# ecocar_CVM.net
KiCad netlist of a schematic drawn in EAGLE
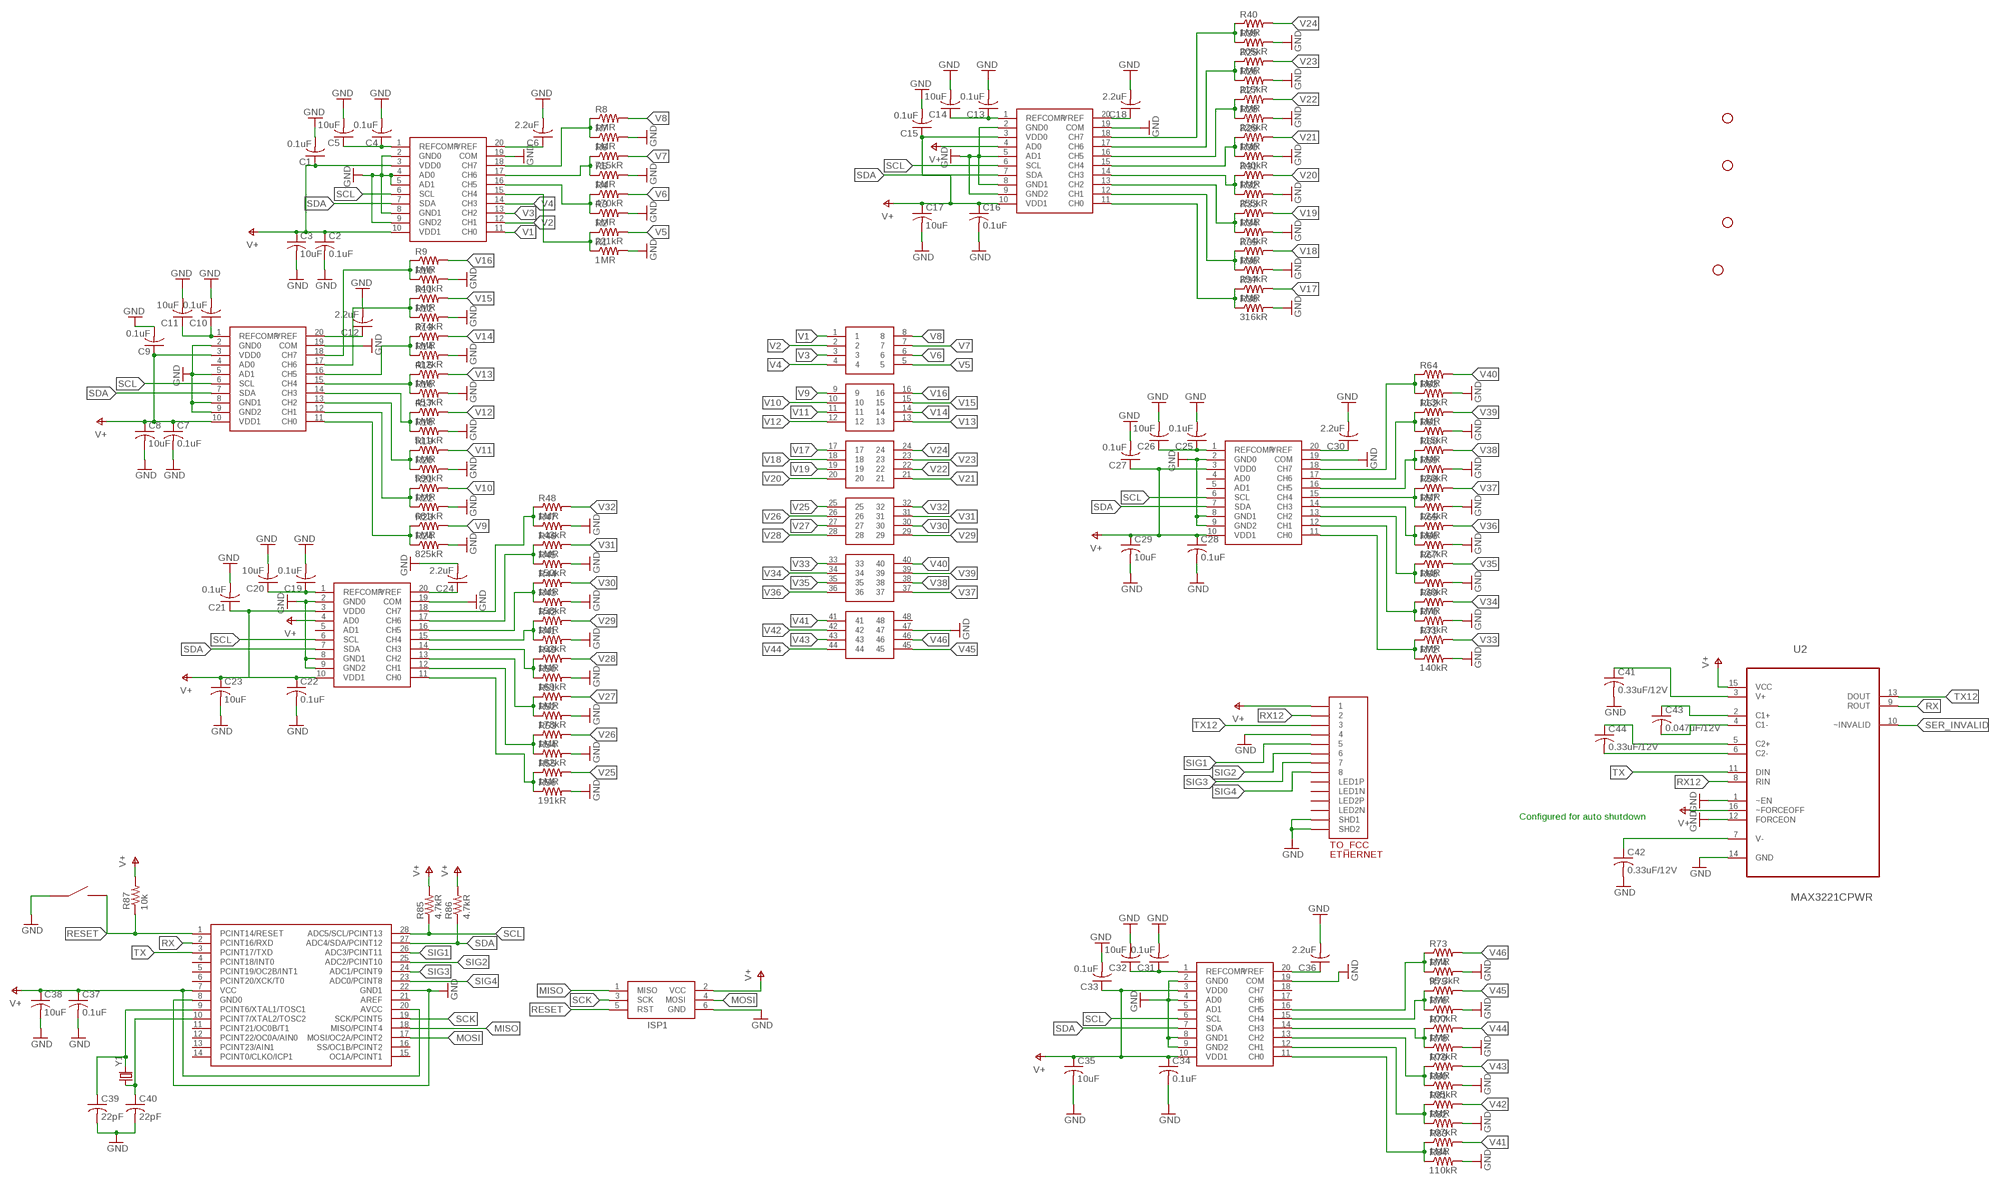
[diagram p0: schematic, sheet 1]

(export (version "E")
  (design (tool "Eeschema 10.0.6"))
  (components
    (comp (ref "0001000")
      (value "LTC2309")
      (footprint "eagle-import:TSSOP20")
      (libsource (lib "eagle-import") (part "LTC2309HF#PBF"))
    )
    (comp (ref "0001001")
      (value "LTC2309")
      (footprint "eagle-import:TSSOP20")
      (libsource (lib "eagle-import") (part "LTC2309HF#PBF"))
    )
    (comp (ref "0001010")
      (value "LTC2309")
      (footprint "eagle-import:TSSOP20")
      (libsource (lib "eagle-import") (part "LTC2309HF#PBF"))
    )
    (comp (ref "0001011")
      (value "LTC2309")
      (footprint "eagle-import:TSSOP20")
      (libsource (lib "eagle-import") (part "LTC2309HF#PBF"))
    )
    (comp (ref "0011000")
      (value "LTC2309")
      (footprint "eagle-import:TSSOP20")
      (libsource (lib "eagle-import") (part "LTC2309HF#PBF"))
    )
    (comp (ref "0011001")
      (value "LTC2309")
      (footprint "eagle-import:TSSOP20")
      (libsource (lib "eagle-import") (part "LTC2309HF#PBF"))
    )
    (comp (ref "C1")
      (value "0.1uF")
      (footprint "eagle-import:C0805")
      (libsource (lib "eagle-import") (part "rcl_C-USC0805"))
    )
    (comp (ref "C2")
      (value "0.1uF")
      (footprint "eagle-import:C0805")
      (libsource (lib "eagle-import") (part "rcl_C-USC0805"))
    )
    (comp (ref "C3")
      (value "10uF")
      (footprint "eagle-import:C0805")
      (libsource (lib "eagle-import") (part "rcl_C-USC0805"))
    )
    (comp (ref "C4")
      (value "0.1uF")
      (footprint "eagle-import:C0805")
      (libsource (lib "eagle-import") (part "rcl_C-USC0805"))
    )
    (comp (ref "C5")
      (value "10uF")
      (footprint "eagle-import:C0805")
      (libsource (lib "eagle-import") (part "rcl_C-USC0805"))
    )
    (comp (ref "C6")
      (value "2.2uF")
      (footprint "eagle-import:C0805")
      (libsource (lib "eagle-import") (part "rcl_C-USC0805"))
    )
    (comp (ref "C7")
      (value "0.1uF")
      (footprint "eagle-import:C0805")
      (libsource (lib "eagle-import") (part "rcl_C-USC0805"))
    )
    (comp (ref "C8")
      (value "10uF")
      (footprint "eagle-import:C0805")
      (libsource (lib "eagle-import") (part "rcl_C-USC0805"))
    )
    (comp (ref "C9")
      (value "0.1uF")
      (footprint "eagle-import:C0805")
      (libsource (lib "eagle-import") (part "rcl_C-USC0805"))
    )
    (comp (ref "C10")
      (value "0.1uF")
      (footprint "eagle-import:C0805")
      (libsource (lib "eagle-import") (part "rcl_C-USC0805"))
    )
    (comp (ref "C11")
      (value "10uF")
      (footprint "eagle-import:C0805")
      (libsource (lib "eagle-import") (part "rcl_C-USC0805"))
    )
    (comp (ref "C12")
      (value "2.2uF")
      (footprint "eagle-import:C0805")
      (libsource (lib "eagle-import") (part "rcl_C-USC0805"))
    )
    (comp (ref "C13")
      (value "0.1uF")
      (footprint "eagle-import:C0805")
      (libsource (lib "eagle-import") (part "rcl_C-USC0805"))
    )
    (comp (ref "C14")
      (value "10uF")
      (footprint "eagle-import:C0805")
      (libsource (lib "eagle-import") (part "rcl_C-USC0805"))
    )
    (comp (ref "C15")
      (value "0.1uF")
      (footprint "eagle-import:C0805")
      (libsource (lib "eagle-import") (part "rcl_C-USC0805"))
    )
    (comp (ref "C16")
      (value "0.1uF")
      (footprint "eagle-import:C0805")
      (libsource (lib "eagle-import") (part "rcl_C-USC0805"))
    )
    (comp (ref "C17")
      (value "10uF")
      (footprint "eagle-import:C0805")
      (libsource (lib "eagle-import") (part "rcl_C-USC0805"))
    )
    (comp (ref "C18")
      (value "2.2uF")
      (footprint "eagle-import:C0805")
      (libsource (lib "eagle-import") (part "rcl_C-USC0805"))
    )
    (comp (ref "C19")
      (value "0.1uF")
      (footprint "eagle-import:C0805")
      (libsource (lib "eagle-import") (part "rcl_C-USC0805"))
    )
    (comp (ref "C20")
      (value "10uF")
      (footprint "eagle-import:C0805")
      (libsource (lib "eagle-import") (part "rcl_C-USC0805"))
    )
    (comp (ref "C21")
      (value "0.1uF")
      (footprint "eagle-import:C0805")
      (libsource (lib "eagle-import") (part "rcl_C-USC0805"))
    )
    (comp (ref "C22")
      (value "0.1uF")
      (footprint "eagle-import:C0805")
      (libsource (lib "eagle-import") (part "rcl_C-USC0805"))
    )
    (comp (ref "C23")
      (value "10uF")
      (footprint "eagle-import:C0805")
      (libsource (lib "eagle-import") (part "rcl_C-USC0805"))
    )
    (comp (ref "C24")
      (value "2.2uF")
      (footprint "eagle-import:C0805")
      (libsource (lib "eagle-import") (part "rcl_C-USC0805"))
    )
    (comp (ref "C25")
      (value "0.1uF")
      (footprint "eagle-import:C0805")
      (libsource (lib "eagle-import") (part "rcl_C-USC0805"))
    )
    (comp (ref "C26")
      (value "10uF")
      (footprint "eagle-import:C0805")
      (libsource (lib "eagle-import") (part "rcl_C-USC0805"))
    )
    (comp (ref "C27")
      (value "0.1uF")
      (footprint "eagle-import:C0805")
      (libsource (lib "eagle-import") (part "rcl_C-USC0805"))
    )
    (comp (ref "C28")
      (value "0.1uF")
      (footprint "eagle-import:C0805")
      (libsource (lib "eagle-import") (part "rcl_C-USC0805"))
    )
    (comp (ref "C29")
      (value "10uF")
      (footprint "eagle-import:C0805")
      (libsource (lib "eagle-import") (part "rcl_C-USC0805"))
    )
    (comp (ref "C30")
      (value "2.2uF")
      (footprint "eagle-import:C0805")
      (libsource (lib "eagle-import") (part "rcl_C-USC0805"))
    )
    (comp (ref "C31")
      (value "0.1uF")
      (footprint "eagle-import:C0805")
      (libsource (lib "eagle-import") (part "rcl_C-USC0805"))
    )
    (comp (ref "C32")
      (value "10uF")
      (footprint "eagle-import:C0805")
      (libsource (lib "eagle-import") (part "rcl_C-USC0805"))
    )
    (comp (ref "C33")
      (value "0.1uF")
      (footprint "eagle-import:C0805")
      (libsource (lib "eagle-import") (part "rcl_C-USC0805"))
    )
    (comp (ref "C34")
      (value "0.1uF")
      (footprint "eagle-import:C0805")
      (libsource (lib "eagle-import") (part "rcl_C-USC0805"))
    )
    (comp (ref "C35")
      (value "10uF")
      (footprint "eagle-import:C0805")
      (libsource (lib "eagle-import") (part "rcl_C-USC0805"))
    )
    (comp (ref "C36")
      (value "2.2uF")
      (footprint "eagle-import:C0805")
      (libsource (lib "eagle-import") (part "rcl_C-USC0805"))
    )
    (comp (ref "C37")
      (value "0.1uF")
      (footprint "eagle-import:C0805")
      (libsource (lib "eagle-import") (part "rcl_C-USC0805"))
    )
    (comp (ref "C38")
      (value "10uF")
      (footprint "eagle-import:C0805")
      (libsource (lib "eagle-import") (part "rcl_C-USC0805"))
    )
    (comp (ref "C39")
      (value "22pF")
      (footprint "eagle-import:C0805")
      (libsource (lib "eagle-import") (part "rcl_C-USC0805"))
    )
    (comp (ref "C40")
      (value "22pF")
      (footprint "eagle-import:C0805")
      (libsource (lib "eagle-import") (part "rcl_C-USC0805"))
    )
    (comp (ref "C41")
      (value "0.33uF/12V")
      (footprint "eagle-import:C0805")
      (libsource (lib "eagle-import") (part "C-USC0805"))
    )
    (comp (ref "C42")
      (value "0.33uF/12V")
      (footprint "eagle-import:C0805")
      (libsource (lib "eagle-import") (part "C-USC0805"))
    )
    (comp (ref "C43")
      (value "0.047uF/12V")
      (footprint "eagle-import:C0805")
      (libsource (lib "eagle-import") (part "C-USC0805"))
    )
    (comp (ref "C44")
      (value "0.33uF/12V")
      (footprint "eagle-import:C0805")
      (libsource (lib "eagle-import") (part "C-USC0805"))
    )
    (comp (ref "ISP1")
      (value "AVRISP-BOX")
      (footprint "eagle-import:AVRISP-BOX")
      (libsource (lib "eagle-import") (part "AVRISP-BOX"))
    )
    (comp (ref "R1")
      (value "1MR")
      (footprint "eagle-import:R0805")
      (libsource (lib "eagle-import") (part "R-US_R0805"))
    )
    (comp (ref "R2")
      (value "221kR")
      (footprint "eagle-import:R0805")
      (libsource (lib "eagle-import") (part "R-US_R0805"))
    )
    (comp (ref "R3")
      (value "1MR")
      (footprint "eagle-import:R0805")
      (libsource (lib "eagle-import") (part "R-US_R0805"))
    )
    (comp (ref "R4")
      (value "470kR")
      (footprint "eagle-import:R0805")
      (libsource (lib "eagle-import") (part "R-US_R0805"))
    )
    (comp (ref "R5")
      (value "1MR")
      (footprint "eagle-import:R0805")
      (libsource (lib "eagle-import") (part "R-US_R0805"))
    )
    (comp (ref "R6")
      (value "715kR")
      (footprint "eagle-import:R0805")
      (libsource (lib "eagle-import") (part "R-US_R0805"))
    )
    (comp (ref "R7")
      (value "1MR")
      (footprint "eagle-import:R0805")
      (libsource (lib "eagle-import") (part "R-US_R0805"))
    )
    (comp (ref "R8")
      (value "1MR")
      (footprint "eagle-import:R0805")
      (libsource (lib "eagle-import") (part "R-US_R0805"))
    )
    (comp (ref "R9")
      (value "1MR")
      (footprint "eagle-import:R0805")
      (libsource (lib "eagle-import") (part "R-US_R0805"))
    )
    (comp (ref "R10")
      (value "340kR")
      (footprint "eagle-import:R0805")
      (libsource (lib "eagle-import") (part "R-US_R0805"))
    )
    (comp (ref "R11")
      (value "1MR")
      (footprint "eagle-import:R0805")
      (libsource (lib "eagle-import") (part "R-US_R0805"))
    )
    (comp (ref "R12")
      (value "374kR")
      (footprint "eagle-import:R0805")
      (libsource (lib "eagle-import") (part "R-US_R0805"))
    )
    (comp (ref "R13")
      (value "1MR")
      (footprint "eagle-import:R0805")
      (libsource (lib "eagle-import") (part "R-US_R0805"))
    )
    (comp (ref "R14")
      (value "412kR")
      (footprint "eagle-import:R0805")
      (libsource (lib "eagle-import") (part "R-US_R0805"))
    )
    (comp (ref "R15")
      (value "1MR")
      (footprint "eagle-import:R0805")
      (libsource (lib "eagle-import") (part "R-US_R0805"))
    )
    (comp (ref "R16")
      (value "453kR")
      (footprint "eagle-import:R0805")
      (libsource (lib "eagle-import") (part "R-US_R0805"))
    )
    (comp (ref "R17")
      (value "1MR")
      (footprint "eagle-import:R0805")
      (libsource (lib "eagle-import") (part "R-US_R0805"))
    )
    (comp (ref "R18")
      (value "511kR")
      (footprint "eagle-import:R0805")
      (libsource (lib "eagle-import") (part "R-US_R0805"))
    )
    (comp (ref "R19")
      (value "1MR")
      (footprint "eagle-import:R0805")
      (libsource (lib "eagle-import") (part "R-US_R0805"))
    )
    (comp (ref "R20")
      (value "590kR")
      (footprint "eagle-import:R0805")
      (libsource (lib "eagle-import") (part "R-US_R0805"))
    )
    (comp (ref "R21")
      (value "1MR")
      (footprint "eagle-import:R0805")
      (libsource (lib "eagle-import") (part "R-US_R0805"))
    )
    (comp (ref "R22")
      (value "681kR")
      (footprint "eagle-import:R0805")
      (libsource (lib "eagle-import") (part "R-US_R0805"))
    )
    (comp (ref "R23")
      (value "1MR")
      (footprint "eagle-import:R0805")
      (libsource (lib "eagle-import") (part "R-US_R0805"))
    )
    (comp (ref "R24")
      (value "825kR")
      (footprint "eagle-import:R0805")
      (libsource (lib "eagle-import") (part "R-US_R0805"))
    )
    (comp (ref "R25")
      (value "1MR")
      (footprint "eagle-import:R0805")
      (libsource (lib "eagle-import") (part "R-US_R0805"))
    )
    (comp (ref "R26")
      (value "215kR")
      (footprint "eagle-import:R0805")
      (libsource (lib "eagle-import") (part "R-US_R0805"))
    )
    (comp (ref "R27")
      (value "1MR")
      (footprint "eagle-import:R0805")
      (libsource (lib "eagle-import") (part "R-US_R0805"))
    )
    (comp (ref "R28")
      (value "226kR")
      (footprint "eagle-import:R0805")
      (libsource (lib "eagle-import") (part "R-US_R0805"))
    )
    (comp (ref "R29")
      (value "1MR")
      (footprint "eagle-import:R0805")
      (libsource (lib "eagle-import") (part "R-US_R0805"))
    )
    (comp (ref "R30")
      (value "240kR")
      (footprint "eagle-import:R0805")
      (libsource (lib "eagle-import") (part "R-US_R0805"))
    )
    (comp (ref "R31")
      (value "1MR")
      (footprint "eagle-import:R0805")
      (libsource (lib "eagle-import") (part "R-US_R0805"))
    )
    (comp (ref "R32")
      (value "255kR")
      (footprint "eagle-import:R0805")
      (libsource (lib "eagle-import") (part "R-US_R0805"))
    )
    (comp (ref "R33")
      (value "1MR")
      (footprint "eagle-import:R0805")
      (libsource (lib "eagle-import") (part "R-US_R0805"))
    )
    (comp (ref "R34")
      (value "274kR")
      (footprint "eagle-import:R0805")
      (libsource (lib "eagle-import") (part "R-US_R0805"))
    )
    (comp (ref "R35")
      (value "1MR")
      (footprint "eagle-import:R0805")
      (libsource (lib "eagle-import") (part "R-US_R0805"))
    )
    (comp (ref "R36")
      (value "294kR")
      (footprint "eagle-import:R0805")
      (libsource (lib "eagle-import") (part "R-US_R0805"))
    )
    (comp (ref "R37")
      (value "1MR")
      (footprint "eagle-import:R0805")
      (libsource (lib "eagle-import") (part "R-US_R0805"))
    )
    (comp (ref "R38")
      (value "316kR")
      (footprint "eagle-import:R0805")
      (libsource (lib "eagle-import") (part "R-US_R0805"))
    )
    (comp (ref "R39")
      (value "205kR")
      (footprint "eagle-import:R0805")
      (libsource (lib "eagle-import") (part "R-US_R0805"))
    )
    (comp (ref "R40")
      (value "1MR")
      (footprint "eagle-import:R0805")
      (libsource (lib "eagle-import") (part "R-US_R0805"))
    )
    (comp (ref "R41")
      (value "162kR")
      (footprint "eagle-import:R0805")
      (libsource (lib "eagle-import") (part "R-US_R0805"))
    )
    (comp (ref "R42")
      (value "1MR")
      (footprint "eagle-import:R0805")
      (libsource (lib "eagle-import") (part "R-US_R0805"))
    )
    (comp (ref "R43")
      (value "158kR")
      (footprint "eagle-import:R0805")
      (libsource (lib "eagle-import") (part "R-US_R0805"))
    )
    (comp (ref "R44")
      (value "1MR")
      (footprint "eagle-import:R0805")
      (libsource (lib "eagle-import") (part "R-US_R0805"))
    )
    (comp (ref "R45")
      (value "150kR")
      (footprint "eagle-import:R0805")
      (libsource (lib "eagle-import") (part "R-US_R0805"))
    )
    (comp (ref "R46")
      (value "1MR")
      (footprint "eagle-import:R0805")
      (libsource (lib "eagle-import") (part "R-US_R0805"))
    )
    (comp (ref "R47")
      (value "143kR")
      (footprint "eagle-import:R0805")
      (libsource (lib "eagle-import") (part "R-US_R0805"))
    )
    (comp (ref "R48")
      (value "1MR")
      (footprint "eagle-import:R0805")
      (libsource (lib "eagle-import") (part "R-US_R0805"))
    )
    (comp (ref "R49")
      (value "1MR")
      (footprint "eagle-import:R0805")
      (libsource (lib "eagle-import") (part "R-US_R0805"))
    )
    (comp (ref "R50")
      (value "169kR")
      (footprint "eagle-import:R0805")
      (libsource (lib "eagle-import") (part "R-US_R0805"))
    )
    (comp (ref "R51")
      (value "1MR")
      (footprint "eagle-import:R0805")
      (libsource (lib "eagle-import") (part "R-US_R0805"))
    )
    (comp (ref "R52")
      (value "178kR")
      (footprint "eagle-import:R0805")
      (libsource (lib "eagle-import") (part "R-US_R0805"))
    )
    (comp (ref "R53")
      (value "1MR")
      (footprint "eagle-import:R0805")
      (libsource (lib "eagle-import") (part "R-US_R0805"))
    )
    (comp (ref "R54")
      (value "182kR")
      (footprint "eagle-import:R0805")
      (libsource (lib "eagle-import") (part "R-US_R0805"))
    )
    (comp (ref "R55")
      (value "1MR")
      (footprint "eagle-import:R0805")
      (libsource (lib "eagle-import") (part "R-US_R0805"))
    )
    (comp (ref "R56")
      (value "191kR")
      (footprint "eagle-import:R0805")
      (libsource (lib "eagle-import") (part "R-US_R0805"))
    )
    (comp (ref "R57")
      (value "124kR")
      (footprint "eagle-import:R0805")
      (libsource (lib "eagle-import") (part "R-US_R0805"))
    )
    (comp (ref "R58")
      (value "1MR")
      (footprint "eagle-import:R0805")
      (libsource (lib "eagle-import") (part "R-US_R0805"))
    )
    (comp (ref "R59")
      (value "120kR")
      (footprint "eagle-import:R0805")
      (libsource (lib "eagle-import") (part "R-US_R0805"))
    )
    (comp (ref "R60")
      (value "1MR")
      (footprint "eagle-import:R0805")
      (libsource (lib "eagle-import") (part "R-US_R0805"))
    )
    (comp (ref "R61")
      (value "115kR")
      (footprint "eagle-import:R0805")
      (libsource (lib "eagle-import") (part "R-US_R0805"))
    )
    (comp (ref "R62")
      (value "1MR")
      (footprint "eagle-import:R0805")
      (libsource (lib "eagle-import") (part "R-US_R0805"))
    )
    (comp (ref "R63")
      (value "113kR")
      (footprint "eagle-import:R0805")
      (libsource (lib "eagle-import") (part "R-US_R0805"))
    )
    (comp (ref "R64")
      (value "1MR")
      (footprint "eagle-import:R0805")
      (libsource (lib "eagle-import") (part "R-US_R0805"))
    )
    (comp (ref "R65")
      (value "1MR")
      (footprint "eagle-import:R0805")
      (libsource (lib "eagle-import") (part "R-US_R0805"))
    )
    (comp (ref "R66")
      (value "127kR")
      (footprint "eagle-import:R0805")
      (libsource (lib "eagle-import") (part "R-US_R0805"))
    )
    (comp (ref "R67")
      (value "1MR")
      (footprint "eagle-import:R0805")
      (libsource (lib "eagle-import") (part "R-US_R0805"))
    )
    (comp (ref "R68")
      (value "130kR")
      (footprint "eagle-import:R0805")
      (libsource (lib "eagle-import") (part "R-US_R0805"))
    )
    (comp (ref "R69")
      (value "1MR")
      (footprint "eagle-import:R0805")
      (libsource (lib "eagle-import") (part "R-US_R0805"))
    )
    (comp (ref "R70")
      (value "133kR")
      (footprint "eagle-import:R0805")
      (libsource (lib "eagle-import") (part "R-US_R0805"))
    )
    (comp (ref "R71")
      (value "1MR")
      (footprint "eagle-import:R0805")
      (libsource (lib "eagle-import") (part "R-US_R0805"))
    )
    (comp (ref "R72")
      (value "140kR")
      (footprint "eagle-import:R0805")
      (libsource (lib "eagle-import") (part "R-US_R0805"))
    )
    (comp (ref "R73")
      (value "1MR")
      (footprint "eagle-import:R0805")
      (libsource (lib "eagle-import") (part "R-US_R0805"))
    )
    (comp (ref "R74")
      (value "95.3kR")
      (footprint "eagle-import:R0805")
      (libsource (lib "eagle-import") (part "R-US_R0805"))
    )
    (comp (ref "R75")
      (value "1MR")
      (footprint "eagle-import:R0805")
      (libsource (lib "eagle-import") (part "R-US_R0805"))
    )
    (comp (ref "R76")
      (value "100kR")
      (footprint "eagle-import:R0805")
      (libsource (lib "eagle-import") (part "R-US_R0805"))
    )
    (comp (ref "R77")
      (value "1MR")
      (footprint "eagle-import:R0805")
      (libsource (lib "eagle-import") (part "R-US_R0805"))
    )
    (comp (ref "R78")
      (value "102kR")
      (footprint "eagle-import:R0805")
      (libsource (lib "eagle-import") (part "R-US_R0805"))
    )
    (comp (ref "R79")
      (value "1MR")
      (footprint "eagle-import:R0805")
      (libsource (lib "eagle-import") (part "R-US_R0805"))
    )
    (comp (ref "R80")
      (value "105kR")
      (footprint "eagle-import:R0805")
      (libsource (lib "eagle-import") (part "R-US_R0805"))
    )
    (comp (ref "R81")
      (value "1MR")
      (footprint "eagle-import:R0805")
      (libsource (lib "eagle-import") (part "R-US_R0805"))
    )
    (comp (ref "R82")
      (value "107kR")
      (footprint "eagle-import:R0805")
      (libsource (lib "eagle-import") (part "R-US_R0805"))
    )
    (comp (ref "R83")
      (value "1MR")
      (footprint "eagle-import:R0805")
      (libsource (lib "eagle-import") (part "R-US_R0805"))
    )
    (comp (ref "R84")
      (value "110kR")
      (footprint "eagle-import:R0805")
      (libsource (lib "eagle-import") (part "R-US_R0805"))
    )
    (comp (ref "R85")
      (value "4.7kR")
      (footprint "eagle-import:R0805")
      (libsource (lib "eagle-import") (part "R-US_R0805"))
    )
    (comp (ref "R86")
      (value "4.7kR")
      (footprint "eagle-import:R0805")
      (libsource (lib "eagle-import") (part "R-US_R0805"))
    )
    (comp (ref "R87")
      (value "10k")
      (footprint "eagle-import:R0805")
      (libsource (lib "eagle-import") (part "R-US_R0805"))
    )
    (comp (ref "STANDOFF1")
      (value "STAND-OFF")
      (footprint "eagle-import:STAND-OFF")
      (libsource (lib "eagle-import") (part "STAND-OFF"))
    )
    (comp (ref "STANDOFF2")
      (value "STAND-OFF")
      (footprint "eagle-import:STAND-OFF")
      (libsource (lib "eagle-import") (part "STAND-OFF"))
    )
    (comp (ref "STANDOFF3")
      (value "STAND-OFF")
      (footprint "eagle-import:STAND-OFF")
      (libsource (lib "eagle-import") (part "STAND-OFF"))
    )
    (comp (ref "STANDOFF4")
      (value "STAND-OFF")
      (footprint "eagle-import:STAND-OFF")
      (libsource (lib "eagle-import") (part "STAND-OFF"))
    )
    (comp (ref "TO_FCC")
      (value "ETHERNET")
      (footprint "eagle-import:A122645-ND")
      (libsource (lib "eagle-import") (part "ETHERNET"))
    )
    (comp (ref "U$1")
      (value "ATMEGA328P")
      (footprint "eagle-import:DIL28-3")
      (libsource (lib "eagle-import") (part "ATMEGA328P"))
    )
    (comp (ref "U$3")
      (value "6-RJ45")
      (footprint "eagle-import:48-PIN-THROUGHHOLE")
      (libsource (lib "eagle-import") (part "6-RJ45-5557572-3"))
    )
    (comp (ref "U$4")
      (value "EG4621CT-ND")
      (footprint "eagle-import:EG4621CT-ND")
      (libsource (lib "eagle-import") (part "EG4621CT-ND"))
    )
    (comp (ref "U2")
      (value "MAX3221CPWR")
      (footprint "eagle-import:SOP65P640X120-16N")
      (libsource (lib "eagle-import") (part "MAX3221CPWR"))
    )
    (comp (ref "Y1")
      (value "CRYSTALHC49US")
      (footprint "eagle-import:HC49US")
      (libsource (lib "eagle-import") (part "CRYSTALHC49US"))
    )
  )
  (nets
    (net (code "1") (name "GND") (class "Default")
      (node (ref "0001000") (pin "19") (pinfunction "COM_19") (pintype "bidirectional"))
      (node (ref "0001000") (pin "2") (pinfunction "GND0_2") (pintype "bidirectional"))
      (node (ref "0001000") (pin "4") (pinfunction "AD0_4") (pintype "bidirectional"))
      (node (ref "0001000") (pin "5") (pinfunction "AD1_5") (pintype "bidirectional"))
      (node (ref "0001000") (pin "8") (pinfunction "GND1_8") (pintype "bidirectional"))
      (node (ref "0001000") (pin "9") (pinfunction "GND2_9") (pintype "bidirectional"))
      (node (ref "0001001") (pin "19") (pinfunction "COM_19") (pintype "bidirectional"))
      (node (ref "0001001") (pin "2") (pinfunction "GND0_2") (pintype "bidirectional"))
      (node (ref "0001001") (pin "5") (pinfunction "AD1_5") (pintype "bidirectional"))
      (node (ref "0001001") (pin "8") (pinfunction "GND1_8") (pintype "bidirectional"))
      (node (ref "0001001") (pin "9") (pinfunction "GND2_9") (pintype "bidirectional"))
      (node (ref "0001010") (pin "19") (pinfunction "COM_19") (pintype "bidirectional"))
      (node (ref "0001010") (pin "2") (pinfunction "GND0_2") (pintype "bidirectional"))
      (node (ref "0001010") (pin "5") (pinfunction "AD1_5") (pintype "bidirectional"))
      (node (ref "0001010") (pin "8") (pinfunction "GND1_8") (pintype "bidirectional"))
      (node (ref "0001010") (pin "9") (pinfunction "GND2_9") (pintype "bidirectional"))
      (node (ref "0001011") (pin "19") (pinfunction "COM_19") (pintype "bidirectional"))
      (node (ref "0001011") (pin "2") (pinfunction "GND0_2") (pintype "bidirectional"))
      (node (ref "0001011") (pin "8") (pinfunction "GND1_8") (pintype "bidirectional"))
      (node (ref "0001011") (pin "9") (pinfunction "GND2_9") (pintype "bidirectional"))
      (node (ref "0011000") (pin "19") (pinfunction "COM_19") (pintype "bidirectional"))
      (node (ref "0011000") (pin "2") (pinfunction "GND0_2") (pintype "bidirectional"))
      (node (ref "0011000") (pin "8") (pinfunction "GND1_8") (pintype "bidirectional"))
      (node (ref "0011000") (pin "9") (pinfunction "GND2_9") (pintype "bidirectional"))
      (node (ref "0011001") (pin "19") (pinfunction "COM_19") (pintype "bidirectional"))
      (node (ref "0011001") (pin "2") (pinfunction "GND0_2") (pintype "bidirectional"))
      (node (ref "0011001") (pin "4") (pinfunction "AD0_4") (pintype "bidirectional"))
      (node (ref "0011001") (pin "8") (pinfunction "GND1_8") (pintype "bidirectional"))
      (node (ref "0011001") (pin "9") (pinfunction "GND2_9") (pintype "bidirectional"))
      (node (ref "C1") (pin "2") (pinfunction "2_2") (pintype "passive"))
      (node (ref "C10") (pin "2") (pinfunction "2_2") (pintype "passive"))
      (node (ref "C11") (pin "2") (pinfunction "2_2") (pintype "passive"))
      (node (ref "C12") (pin "2") (pinfunction "2_2") (pintype "passive"))
      (node (ref "C13") (pin "2") (pinfunction "2_2") (pintype "passive"))
      (node (ref "C14") (pin "2") (pinfunction "2_2") (pintype "passive"))
      (node (ref "C15") (pin "2") (pinfunction "2_2") (pintype "passive"))
      (node (ref "C16") (pin "2") (pinfunction "2_2") (pintype "passive"))
      (node (ref "C17") (pin "2") (pinfunction "2_2") (pintype "passive"))
      (node (ref "C18") (pin "2") (pinfunction "2_2") (pintype "passive"))
      (node (ref "C19") (pin "2") (pinfunction "2_2") (pintype "passive"))
      (node (ref "C2") (pin "2") (pinfunction "2_2") (pintype "passive"))
      (node (ref "C20") (pin "2") (pinfunction "2_2") (pintype "passive"))
      (node (ref "C21") (pin "2") (pinfunction "2_2") (pintype "passive"))
      (node (ref "C22") (pin "2") (pinfunction "2_2") (pintype "passive"))
      (node (ref "C23") (pin "2") (pinfunction "2_2") (pintype "passive"))
      (node (ref "C24") (pin "2") (pinfunction "2_2") (pintype "passive"))
      (node (ref "C25") (pin "2") (pinfunction "2_2") (pintype "passive"))
      (node (ref "C26") (pin "2") (pinfunction "2_2") (pintype "passive"))
      (node (ref "C27") (pin "2") (pinfunction "2_2") (pintype "passive"))
      (node (ref "C28") (pin "2") (pinfunction "2_2") (pintype "passive"))
      (node (ref "C29") (pin "2") (pinfunction "2_2") (pintype "passive"))
      (node (ref "C3") (pin "2") (pinfunction "2_2") (pintype "passive"))
      (node (ref "C30") (pin "2") (pinfunction "2_2") (pintype "passive"))
      (node (ref "C31") (pin "2") (pinfunction "2_2") (pintype "passive"))
      (node (ref "C32") (pin "2") (pinfunction "2_2") (pintype "passive"))
      (node (ref "C33") (pin "2") (pinfunction "2_2") (pintype "passive"))
      (node (ref "C34") (pin "2") (pinfunction "2_2") (pintype "passive"))
      (node (ref "C35") (pin "2") (pinfunction "2_2") (pintype "passive"))
      (node (ref "C36") (pin "2") (pinfunction "2_2") (pintype "passive"))
      (node (ref "C37") (pin "2") (pinfunction "2_2") (pintype "passive"))
      (node (ref "C38") (pin "2") (pinfunction "2_2") (pintype "passive"))
      (node (ref "C39") (pin "2") (pinfunction "2_2") (pintype "passive"))
      (node (ref "C4") (pin "2") (pinfunction "2_2") (pintype "passive"))
      (node (ref "C40") (pin "2") (pinfunction "2_2") (pintype "passive"))
      (node (ref "C41") (pin "2") (pinfunction "2_2") (pintype "passive"))
      (node (ref "C42") (pin "2") (pinfunction "2_2") (pintype "passive"))
      (node (ref "C5") (pin "2") (pinfunction "2_2") (pintype "passive"))
      (node (ref "C6") (pin "2") (pinfunction "2_2") (pintype "passive"))
      (node (ref "C7") (pin "2") (pinfunction "2_2") (pintype "passive"))
      (node (ref "C8") (pin "2") (pinfunction "2_2") (pintype "passive"))
      (node (ref "C9") (pin "2") (pinfunction "2_2") (pintype "passive"))
      (node (ref "ISP1") (pin "6") (pinfunction "GND_6") (pintype "power_in"))
      (node (ref "R1") (pin "2") (pinfunction "2_2") (pintype "passive"))
      (node (ref "R10") (pin "2") (pinfunction "2_2") (pintype "passive"))
      (node (ref "R12") (pin "2") (pinfunction "2_2") (pintype "passive"))
      (node (ref "R14") (pin "2") (pinfunction "2_2") (pintype "passive"))
      (node (ref "R16") (pin "2") (pinfunction "2_2") (pintype "passive"))
      (node (ref "R18") (pin "2") (pinfunction "2_2") (pintype "passive"))
      (node (ref "R20") (pin "2") (pinfunction "2_2") (pintype "passive"))
      (node (ref "R22") (pin "2") (pinfunction "2_2") (pintype "passive"))
      (node (ref "R24") (pin "2") (pinfunction "2_2") (pintype "passive"))
      (node (ref "R26") (pin "2") (pinfunction "2_2") (pintype "passive"))
      (node (ref "R28") (pin "2") (pinfunction "2_2") (pintype "passive"))
      (node (ref "R3") (pin "2") (pinfunction "2_2") (pintype "passive"))
      (node (ref "R30") (pin "2") (pinfunction "2_2") (pintype "passive"))
      (node (ref "R32") (pin "2") (pinfunction "2_2") (pintype "passive"))
      (node (ref "R34") (pin "2") (pinfunction "2_2") (pintype "passive"))
      (node (ref "R36") (pin "2") (pinfunction "2_2") (pintype "passive"))
      (node (ref "R38") (pin "2") (pinfunction "2_2") (pintype "passive"))
      (node (ref "R39") (pin "2") (pinfunction "2_2") (pintype "passive"))
      (node (ref "R41") (pin "2") (pinfunction "2_2") (pintype "passive"))
      (node (ref "R43") (pin "2") (pinfunction "2_2") (pintype "passive"))
      (node (ref "R45") (pin "2") (pinfunction "2_2") (pintype "passive"))
      (node (ref "R47") (pin "2") (pinfunction "2_2") (pintype "passive"))
      (node (ref "R5") (pin "2") (pinfunction "2_2") (pintype "passive"))
      (node (ref "R50") (pin "2") (pinfunction "2_2") (pintype "passive"))
      (node (ref "R52") (pin "2") (pinfunction "2_2") (pintype "passive"))
      (node (ref "R54") (pin "2") (pinfunction "2_2") (pintype "passive"))
      (node (ref "R56") (pin "2") (pinfunction "2_2") (pintype "passive"))
      (node (ref "R57") (pin "2") (pinfunction "2_2") (pintype "passive"))
      (node (ref "R59") (pin "2") (pinfunction "2_2") (pintype "passive"))
      (node (ref "R61") (pin "2") (pinfunction "2_2") (pintype "passive"))
      (node (ref "R63") (pin "2") (pinfunction "2_2") (pintype "passive"))
      (node (ref "R66") (pin "2") (pinfunction "2_2") (pintype "passive"))
      (node (ref "R68") (pin "2") (pinfunction "2_2") (pintype "passive"))
      (node (ref "R7") (pin "2") (pinfunction "2_2") (pintype "passive"))
      (node (ref "R70") (pin "2") (pinfunction "2_2") (pintype "passive"))
      (node (ref "R72") (pin "2") (pinfunction "2_2") (pintype "passive"))
      (node (ref "R74") (pin "2") (pinfunction "2_2") (pintype "passive"))
      (node (ref "R76") (pin "2") (pinfunction "2_2") (pintype "passive"))
      (node (ref "R78") (pin "2") (pinfunction "2_2") (pintype "passive"))
      (node (ref "R80") (pin "2") (pinfunction "2_2") (pintype "passive"))
      (node (ref "R82") (pin "2") (pinfunction "2_2") (pintype "passive"))
      (node (ref "R84") (pin "2") (pinfunction "2_2") (pintype "passive"))
      (node (ref "TO_FCC") (pin "P$13") (pinfunction "SHD1_P$13") (pintype "bidirectional"))
      (node (ref "TO_FCC") (pin "P$14") (pinfunction "SHD2_P$14") (pintype "bidirectional"))
      (node (ref "TO_FCC") (pin "P$4") (pinfunction "4_P$4") (pintype "bidirectional"))
      (node (ref "U$1") (pin "22") (pinfunction "GND1_22") (pintype "bidirectional"))
      (node (ref "U$1") (pin "8") (pinfunction "GND0_8") (pintype "bidirectional"))
      (node (ref "U$3") (pin "47") (pinfunction "47_47") (pintype "bidirectional"))
      (node (ref "U$4") (pin "P$1") (pinfunction "P$1_P$1") (pintype "bidirectional"))
      (node (ref "U$4") (pin "P$2") (pinfunction "P$1_P$2") (pintype "bidirectional"))
      (node (ref "U2") (pin "1") (pinfunction "~{EN}_1") (pintype "input"))
      (node (ref "U2") (pin "12") (pinfunction "FORCEON_12") (pintype "input"))
      (node (ref "U2") (pin "14") (pinfunction "GND_14") (pintype "passive"))
    )
    (net (code "2") (name "MISO") (class "Default")
      (node (ref "ISP1") (pin "1") (pinfunction "MISO_1") (pintype "input"))
      (node (ref "U$1") (pin "18") (pinfunction "MISO/PCINT4_18") (pintype "bidirectional"))
    )
    (net (code "3") (name "MOSI") (class "Default")
      (node (ref "ISP1") (pin "4") (pinfunction "MOSI_4") (pintype "output"))
      (node (ref "U$1") (pin "17") (pinfunction "MOSI/OC2A/PCINT2_17") (pintype "bidirectional"))
    )
    (net (code "4") (name "Net-(0001000-CH4)") (class "Default")
      (node (ref "0001000") (pin "15") (pinfunction "CH4_15") (pintype "bidirectional"))
      (node (ref "R1") (pin "1") (pinfunction "1_1") (pintype "passive"))
      (node (ref "R2") (pin "1") (pinfunction "1_1") (pintype "passive"))
    )
    (net (code "5") (name "Net-(0001000-CH5)") (class "Default")
      (node (ref "0001000") (pin "16") (pinfunction "CH5_16") (pintype "bidirectional"))
      (node (ref "R3") (pin "1") (pinfunction "1_1") (pintype "passive"))
      (node (ref "R4") (pin "1") (pinfunction "1_1") (pintype "passive"))
    )
    (net (code "6") (name "Net-(0001000-CH6)") (class "Default")
      (node (ref "0001000") (pin "17") (pinfunction "CH6_17") (pintype "bidirectional"))
      (node (ref "R5") (pin "1") (pinfunction "1_1") (pintype "passive"))
      (node (ref "R6") (pin "1") (pinfunction "1_1") (pintype "passive"))
    )
    (net (code "7") (name "Net-(0001000-CH7)") (class "Default")
      (node (ref "0001000") (pin "18") (pinfunction "CH7_18") (pintype "bidirectional"))
      (node (ref "R7") (pin "1") (pinfunction "1_1") (pintype "passive"))
      (node (ref "R8") (pin "1") (pinfunction "1_1") (pintype "passive"))
    )
    (net (code "8") (name "Net-(0001000-REFCOMP)") (class "Default")
      (node (ref "0001000") (pin "1") (pinfunction "REFCOMP_1") (pintype "bidirectional"))
      (node (ref "C4") (pin "1") (pinfunction "1_1") (pintype "passive"))
      (node (ref "C5") (pin "1") (pinfunction "1_1") (pintype "passive"))
    )
    (net (code "9") (name "Net-(0001000-VREF)") (class "Default")
      (node (ref "0001000") (pin "20") (pinfunction "VREF_20") (pintype "bidirectional"))
      (node (ref "C6") (pin "1") (pinfunction "1_1") (pintype "passive"))
    )
    (net (code "10") (name "Net-(0001001-CH0)") (class "Default")
      (node (ref "0001001") (pin "11") (pinfunction "CH0_11") (pintype "bidirectional"))
      (node (ref "R23") (pin "1") (pinfunction "1_1") (pintype "passive"))
      (node (ref "R24") (pin "1") (pinfunction "1_1") (pintype "passive"))
    )
    (net (code "11") (name "Net-(0001001-CH1)") (class "Default")
      (node (ref "0001001") (pin "12") (pinfunction "CH1_12") (pintype "bidirectional"))
      (node (ref "R21") (pin "1") (pinfunction "1_1") (pintype "passive"))
      (node (ref "R22") (pin "1") (pinfunction "1_1") (pintype "passive"))
    )
    (net (code "12") (name "Net-(0001001-CH2)") (class "Default")
      (node (ref "0001001") (pin "13") (pinfunction "CH2_13") (pintype "bidirectional"))
      (node (ref "R19") (pin "1") (pinfunction "1_1") (pintype "passive"))
      (node (ref "R20") (pin "1") (pinfunction "1_1") (pintype "passive"))
    )
    (net (code "13") (name "Net-(0001001-CH3)") (class "Default")
      (node (ref "0001001") (pin "14") (pinfunction "CH3_14") (pintype "bidirectional"))
      (node (ref "R17") (pin "1") (pinfunction "1_1") (pintype "passive"))
      (node (ref "R18") (pin "1") (pinfunction "1_1") (pintype "passive"))
    )
    (net (code "14") (name "Net-(0001001-CH4)") (class "Default")
      (node (ref "0001001") (pin "15") (pinfunction "CH4_15") (pintype "bidirectional"))
      (node (ref "R15") (pin "1") (pinfunction "1_1") (pintype "passive"))
      (node (ref "R16") (pin "1") (pinfunction "1_1") (pintype "passive"))
    )
    (net (code "15") (name "Net-(0001001-CH5)") (class "Default")
      (node (ref "0001001") (pin "16") (pinfunction "CH5_16") (pintype "bidirectional"))
      (node (ref "R13") (pin "1") (pinfunction "1_1") (pintype "passive"))
      (node (ref "R14") (pin "1") (pinfunction "1_1") (pintype "passive"))
    )
    (net (code "16") (name "Net-(0001001-CH6)") (class "Default")
      (node (ref "0001001") (pin "17") (pinfunction "CH6_17") (pintype "bidirectional"))
      (node (ref "R11") (pin "1") (pinfunction "1_1") (pintype "passive"))
      (node (ref "R12") (pin "1") (pinfunction "1_1") (pintype "passive"))
    )
    (net (code "17") (name "Net-(0001001-CH7)") (class "Default")
      (node (ref "0001001") (pin "18") (pinfunction "CH7_18") (pintype "bidirectional"))
      (node (ref "R10") (pin "1") (pinfunction "1_1") (pintype "passive"))
      (node (ref "R9") (pin "1") (pinfunction "1_1") (pintype "passive"))
    )
    (net (code "18") (name "Net-(0001001-REFCOMP)") (class "Default")
      (node (ref "0001001") (pin "1") (pinfunction "REFCOMP_1") (pintype "bidirectional"))
      (node (ref "C10") (pin "1") (pinfunction "1_1") (pintype "passive"))
      (node (ref "C11") (pin "1") (pinfunction "1_1") (pintype "passive"))
    )
    (net (code "19") (name "Net-(0001001-VREF)") (class "Default")
      (node (ref "0001001") (pin "20") (pinfunction "VREF_20") (pintype "bidirectional"))
      (node (ref "C12") (pin "1") (pinfunction "1_1") (pintype "passive"))
    )
    (net (code "20") (name "Net-(0001010-CH0)") (class "Default")
      (node (ref "0001010") (pin "11") (pinfunction "CH0_11") (pintype "bidirectional"))
      (node (ref "R37") (pin "1") (pinfunction "1_1") (pintype "passive"))
      (node (ref "R38") (pin "1") (pinfunction "1_1") (pintype "passive"))
    )
    (net (code "21") (name "Net-(0001010-CH1)") (class "Default")
      (node (ref "0001010") (pin "12") (pinfunction "CH1_12") (pintype "bidirectional"))
      (node (ref "R35") (pin "1") (pinfunction "1_1") (pintype "passive"))
      (node (ref "R36") (pin "1") (pinfunction "1_1") (pintype "passive"))
    )
    (net (code "22") (name "Net-(0001010-CH2)") (class "Default")
      (node (ref "0001010") (pin "13") (pinfunction "CH2_13") (pintype "bidirectional"))
      (node (ref "R33") (pin "1") (pinfunction "1_1") (pintype "passive"))
      (node (ref "R34") (pin "1") (pinfunction "1_1") (pintype "passive"))
    )
    (net (code "23") (name "Net-(0001010-CH3)") (class "Default")
      (node (ref "0001010") (pin "14") (pinfunction "CH3_14") (pintype "bidirectional"))
      (node (ref "R31") (pin "1") (pinfunction "1_1") (pintype "passive"))
      (node (ref "R32") (pin "1") (pinfunction "1_1") (pintype "passive"))
    )
    (net (code "24") (name "Net-(0001010-CH4)") (class "Default")
      (node (ref "0001010") (pin "15") (pinfunction "CH4_15") (pintype "bidirectional"))
      (node (ref "R29") (pin "1") (pinfunction "1_1") (pintype "passive"))
      (node (ref "R30") (pin "1") (pinfunction "1_1") (pintype "passive"))
    )
    (net (code "25") (name "Net-(0001010-CH5)") (class "Default")
      (node (ref "0001010") (pin "16") (pinfunction "CH5_16") (pintype "bidirectional"))
      (node (ref "R27") (pin "1") (pinfunction "1_1") (pintype "passive"))
      (node (ref "R28") (pin "1") (pinfunction "1_1") (pintype "passive"))
    )
    (net (code "26") (name "Net-(0001010-CH6)") (class "Default")
      (node (ref "0001010") (pin "17") (pinfunction "CH6_17") (pintype "bidirectional"))
      (node (ref "R25") (pin "1") (pinfunction "1_1") (pintype "passive"))
      (node (ref "R26") (pin "1") (pinfunction "1_1") (pintype "passive"))
    )
    (net (code "27") (name "Net-(0001010-CH7)") (class "Default")
      (node (ref "0001010") (pin "18") (pinfunction "CH7_18") (pintype "bidirectional"))
      (node (ref "R39") (pin "1") (pinfunction "1_1") (pintype "passive"))
      (node (ref "R40") (pin "1") (pinfunction "1_1") (pintype "passive"))
    )
    (net (code "28") (name "Net-(0001010-REFCOMP)") (class "Default")
      (node (ref "0001010") (pin "1") (pinfunction "REFCOMP_1") (pintype "bidirectional"))
      (node (ref "C13") (pin "1") (pinfunction "1_1") (pintype "passive"))
      (node (ref "C14") (pin "1") (pinfunction "1_1") (pintype "passive"))
    )
    (net (code "29") (name "Net-(0001010-VREF)") (class "Default")
      (node (ref "0001010") (pin "20") (pinfunction "VREF_20") (pintype "bidirectional"))
      (node (ref "C18") (pin "1") (pinfunction "1_1") (pintype "passive"))
    )
    (net (code "30") (name "Net-(0001011-CH0)") (class "Default")
      (node (ref "0001011") (pin "11") (pinfunction "CH0_11") (pintype "bidirectional"))
      (node (ref "R55") (pin "1") (pinfunction "1_1") (pintype "passive"))
      (node (ref "R56") (pin "1") (pinfunction "1_1") (pintype "passive"))
    )
    (net (code "31") (name "Net-(0001011-CH1)") (class "Default")
      (node (ref "0001011") (pin "12") (pinfunction "CH1_12") (pintype "bidirectional"))
      (node (ref "R53") (pin "1") (pinfunction "1_1") (pintype "passive"))
      (node (ref "R54") (pin "1") (pinfunction "1_1") (pintype "passive"))
    )
    (net (code "32") (name "Net-(0001011-CH2)") (class "Default")
      (node (ref "0001011") (pin "13") (pinfunction "CH2_13") (pintype "bidirectional"))
      (node (ref "R51") (pin "1") (pinfunction "1_1") (pintype "passive"))
      (node (ref "R52") (pin "1") (pinfunction "1_1") (pintype "passive"))
    )
    (net (code "33") (name "Net-(0001011-CH3)") (class "Default")
      (node (ref "0001011") (pin "14") (pinfunction "CH3_14") (pintype "bidirectional"))
      (node (ref "R49") (pin "1") (pinfunction "1_1") (pintype "passive"))
      (node (ref "R50") (pin "1") (pinfunction "1_1") (pintype "passive"))
    )
    (net (code "34") (name "Net-(0001011-CH4)") (class "Default")
      (node (ref "0001011") (pin "15") (pinfunction "CH4_15") (pintype "bidirectional"))
      (node (ref "R41") (pin "1") (pinfunction "1_1") (pintype "passive"))
      (node (ref "R42") (pin "1") (pinfunction "1_1") (pintype "passive"))
    )
    (net (code "35") (name "Net-(0001011-CH5)") (class "Default")
      (node (ref "0001011") (pin "16") (pinfunction "CH5_16") (pintype "bidirectional"))
      (node (ref "R43") (pin "1") (pinfunction "1_1") (pintype "passive"))
      (node (ref "R44") (pin "1") (pinfunction "1_1") (pintype "passive"))
    )
    (net (code "36") (name "Net-(0001011-CH6)") (class "Default")
      (node (ref "0001011") (pin "17") (pinfunction "CH6_17") (pintype "bidirectional"))
      (node (ref "R45") (pin "1") (pinfunction "1_1") (pintype "passive"))
      (node (ref "R46") (pin "1") (pinfunction "1_1") (pintype "passive"))
    )
    (net (code "37") (name "Net-(0001011-CH7)") (class "Default")
      (node (ref "0001011") (pin "18") (pinfunction "CH7_18") (pintype "bidirectional"))
      (node (ref "R47") (pin "1") (pinfunction "1_1") (pintype "passive"))
      (node (ref "R48") (pin "1") (pinfunction "1_1") (pintype "passive"))
    )
    (net (code "38") (name "Net-(0001011-REFCOMP)") (class "Default")
      (node (ref "0001011") (pin "1") (pinfunction "REFCOMP_1") (pintype "bidirectional"))
      (node (ref "C19") (pin "1") (pinfunction "1_1") (pintype "passive"))
      (node (ref "C20") (pin "1") (pinfunction "1_1") (pintype "passive"))
    )
    (net (code "39") (name "Net-(0001011-VREF)") (class "Default")
      (node (ref "0001011") (pin "20") (pinfunction "VREF_20") (pintype "bidirectional"))
      (node (ref "C24") (pin "1") (pinfunction "1_1") (pintype "passive"))
    )
    (net (code "40") (name "Net-(0011000-CH0)") (class "Default")
      (node (ref "0011000") (pin "11") (pinfunction "CH0_11") (pintype "bidirectional"))
      (node (ref "R71") (pin "1") (pinfunction "1_1") (pintype "passive"))
      (node (ref "R72") (pin "1") (pinfunction "1_1") (pintype "passive"))
    )
    (net (code "41") (name "Net-(0011000-CH1)") (class "Default")
      (node (ref "0011000") (pin "12") (pinfunction "CH1_12") (pintype "bidirectional"))
      (node (ref "R69") (pin "1") (pinfunction "1_1") (pintype "passive"))
      (node (ref "R70") (pin "1") (pinfunction "1_1") (pintype "passive"))
    )
    (net (code "42") (name "Net-(0011000-CH2)") (class "Default")
      (node (ref "0011000") (pin "13") (pinfunction "CH2_13") (pintype "bidirectional"))
      (node (ref "R67") (pin "1") (pinfunction "1_1") (pintype "passive"))
      (node (ref "R68") (pin "1") (pinfunction "1_1") (pintype "passive"))
    )
    (net (code "43") (name "Net-(0011000-CH3)") (class "Default")
      (node (ref "0011000") (pin "14") (pinfunction "CH3_14") (pintype "bidirectional"))
      (node (ref "R65") (pin "1") (pinfunction "1_1") (pintype "passive"))
      (node (ref "R66") (pin "1") (pinfunction "1_1") (pintype "passive"))
    )
    (net (code "44") (name "Net-(0011000-CH4)") (class "Default")
      (node (ref "0011000") (pin "15") (pinfunction "CH4_15") (pintype "bidirectional"))
      (node (ref "R57") (pin "1") (pinfunction "1_1") (pintype "passive"))
      (node (ref "R58") (pin "1") (pinfunction "1_1") (pintype "passive"))
    )
    (net (code "45") (name "Net-(0011000-CH5)") (class "Default")
      (node (ref "0011000") (pin "16") (pinfunction "CH5_16") (pintype "bidirectional"))
      (node (ref "R59") (pin "1") (pinfunction "1_1") (pintype "passive"))
      (node (ref "R60") (pin "1") (pinfunction "1_1") (pintype "passive"))
    )
    (net (code "46") (name "Net-(0011000-CH6)") (class "Default")
      (node (ref "0011000") (pin "17") (pinfunction "CH6_17") (pintype "bidirectional"))
      (node (ref "R61") (pin "1") (pinfunction "1_1") (pintype "passive"))
      (node (ref "R62") (pin "1") (pinfunction "1_1") (pintype "passive"))
    )
    (net (code "47") (name "Net-(0011000-CH7)") (class "Default")
      (node (ref "0011000") (pin "18") (pinfunction "CH7_18") (pintype "bidirectional"))
      (node (ref "R63") (pin "1") (pinfunction "1_1") (pintype "passive"))
      (node (ref "R64") (pin "1") (pinfunction "1_1") (pintype "passive"))
    )
    (net (code "48") (name "Net-(0011000-REFCOMP)") (class "Default")
      (node (ref "0011000") (pin "1") (pinfunction "REFCOMP_1") (pintype "bidirectional"))
      (node (ref "C25") (pin "1") (pinfunction "1_1") (pintype "passive"))
      (node (ref "C26") (pin "1") (pinfunction "1_1") (pintype "passive"))
    )
    (net (code "49") (name "Net-(0011000-VREF)") (class "Default")
      (node (ref "0011000") (pin "20") (pinfunction "VREF_20") (pintype "bidirectional"))
      (node (ref "C30") (pin "1") (pinfunction "1_1") (pintype "passive"))
    )
    (net (code "50") (name "Net-(0011001-CH0)") (class "Default")
      (node (ref "0011001") (pin "11") (pinfunction "CH0_11") (pintype "bidirectional"))
      (node (ref "R83") (pin "1") (pinfunction "1_1") (pintype "passive"))
      (node (ref "R84") (pin "1") (pinfunction "1_1") (pintype "passive"))
    )
    (net (code "51") (name "Net-(0011001-CH1)") (class "Default")
      (node (ref "0011001") (pin "12") (pinfunction "CH1_12") (pintype "bidirectional"))
      (node (ref "R81") (pin "1") (pinfunction "1_1") (pintype "passive"))
      (node (ref "R82") (pin "1") (pinfunction "1_1") (pintype "passive"))
    )
    (net (code "52") (name "Net-(0011001-CH2)") (class "Default")
      (node (ref "0011001") (pin "13") (pinfunction "CH2_13") (pintype "bidirectional"))
      (node (ref "R79") (pin "1") (pinfunction "1_1") (pintype "passive"))
      (node (ref "R80") (pin "1") (pinfunction "1_1") (pintype "passive"))
    )
    (net (code "53") (name "Net-(0011001-CH3)") (class "Default")
      (node (ref "0011001") (pin "14") (pinfunction "CH3_14") (pintype "bidirectional"))
      (node (ref "R77") (pin "1") (pinfunction "1_1") (pintype "passive"))
      (node (ref "R78") (pin "1") (pinfunction "1_1") (pintype "passive"))
    )
    (net (code "54") (name "Net-(0011001-CH4)") (class "Default")
      (node (ref "0011001") (pin "15") (pinfunction "CH4_15") (pintype "bidirectional"))
      (node (ref "R75") (pin "1") (pinfunction "1_1") (pintype "passive"))
      (node (ref "R76") (pin "1") (pinfunction "1_1") (pintype "passive"))
    )
    (net (code "55") (name "Net-(0011001-CH5)") (class "Default")
      (node (ref "0011001") (pin "16") (pinfunction "CH5_16") (pintype "bidirectional"))
      (node (ref "R73") (pin "1") (pinfunction "1_1") (pintype "passive"))
      (node (ref "R74") (pin "1") (pinfunction "1_1") (pintype "passive"))
    )
    (net (code "56") (name "Net-(0011001-REFCOMP)") (class "Default")
      (node (ref "0011001") (pin "1") (pinfunction "REFCOMP_1") (pintype "bidirectional"))
      (node (ref "C31") (pin "1") (pinfunction "1_1") (pintype "passive"))
      (node (ref "C32") (pin "1") (pinfunction "1_1") (pintype "passive"))
    )
    (net (code "57") (name "Net-(0011001-VREF)") (class "Default")
      (node (ref "0011001") (pin "20") (pinfunction "VREF_20") (pintype "bidirectional"))
      (node (ref "C36") (pin "1") (pinfunction "1_1") (pintype "passive"))
    )
    (net (code "58") (name "Net-(U$1-PCINT6{slash}XTAL1{slash}TOSC1)") (class "Default")
      (node (ref "C39") (pin "1") (pinfunction "1_1") (pintype "passive"))
      (node (ref "U$1") (pin "9") (pinfunction "PCINT6/XTAL1/TOSC1_9") (pintype "bidirectional"))
      (node (ref "Y1") (pin "2") (pinfunction "2_2") (pintype "passive"))
    )
    (net (code "59") (name "Net-(U$1-PCINT7{slash}XTAL2{slash}TOSC2)") (class "Default")
      (node (ref "C40") (pin "1") (pinfunction "1_1") (pintype "passive"))
      (node (ref "U$1") (pin "10") (pinfunction "PCINT7/XTAL2/TOSC2_10") (pintype "bidirectional"))
      (node (ref "Y1") (pin "1") (pinfunction "1_1") (pintype "passive"))
    )
    (net (code "60") (name "Net-(U2-C1+)") (class "Default")
      (node (ref "C43") (pin "1") (pinfunction "1_1") (pintype "passive"))
      (node (ref "U2") (pin "2") (pinfunction "C1+_2") (pintype "passive"))
    )
    (net (code "61") (name "Net-(U2-C1-)") (class "Default")
      (node (ref "C43") (pin "2") (pinfunction "2_2") (pintype "passive"))
      (node (ref "U2") (pin "4") (pinfunction "C1-_4") (pintype "passive"))
    )
    (net (code "62") (name "Net-(U2-C2+)") (class "Default")
      (node (ref "C44") (pin "1") (pinfunction "1_1") (pintype "passive"))
      (node (ref "U2") (pin "5") (pinfunction "C2+_5") (pintype "passive"))
    )
    (net (code "63") (name "Net-(U2-C2-)") (class "Default")
      (node (ref "C44") (pin "2") (pinfunction "2_2") (pintype "passive"))
      (node (ref "U2") (pin "6") (pinfunction "C2-_6") (pintype "passive"))
    )
    (net (code "64") (name "Net-(U2-V+)") (class "Default")
      (node (ref "C41") (pin "1") (pinfunction "1_1") (pintype "passive"))
      (node (ref "U2") (pin "3") (pinfunction "V+_3") (pintype "power_in"))
    )
    (net (code "65") (name "Net-(U2-V-)") (class "Default")
      (node (ref "C42") (pin "1") (pinfunction "1_1") (pintype "passive"))
      (node (ref "U2") (pin "7") (pinfunction "V-_7") (pintype "power_in"))
    )
    (net (code "66") (name "RESET") (class "Default")
      (node (ref "ISP1") (pin "5") (pinfunction "RST_5") (pintype "output"))
      (node (ref "R87") (pin "1") (pinfunction "1_1") (pintype "passive"))
      (node (ref "U$1") (pin "1") (pinfunction "PCINT14/RESET_1") (pintype "bidirectional"))
      (node (ref "U$4") (pin "P$3") (pinfunction "P$2_P$3") (pintype "bidirectional"))
      (node (ref "U$4") (pin "P$4") (pinfunction "P$2_P$4") (pintype "bidirectional"))
    )
    (net (code "67") (name "RX") (class "Default")
      (node (ref "U$1") (pin "2") (pinfunction "PCINT16/RXD_2") (pintype "bidirectional"))
      (node (ref "U2") (pin "9") (pinfunction "ROUT_9") (pintype "output"))
    )
    (net (code "68") (name "RX12") (class "Default")
      (node (ref "TO_FCC") (pin "P$2") (pinfunction "2_P$2") (pintype "bidirectional"))
      (node (ref "U2") (pin "8") (pinfunction "RIN_8") (pintype "input"))
    )
    (net (code "69") (name "SCK") (class "Default")
      (node (ref "ISP1") (pin "3") (pinfunction "SCK_3") (pintype "output"))
      (node (ref "U$1") (pin "19") (pinfunction "SCK/PCINT5_19") (pintype "bidirectional"))
    )
    (net (code "70") (name "SCL") (class "Default")
      (node (ref "0001000") (pin "6") (pinfunction "SCL_6") (pintype "bidirectional"))
      (node (ref "0001001") (pin "6") (pinfunction "SCL_6") (pintype "bidirectional"))
      (node (ref "0001010") (pin "6") (pinfunction "SCL_6") (pintype "bidirectional"))
      (node (ref "0001011") (pin "6") (pinfunction "SCL_6") (pintype "bidirectional"))
      (node (ref "0011000") (pin "6") (pinfunction "SCL_6") (pintype "bidirectional"))
      (node (ref "0011001") (pin "6") (pinfunction "SCL_6") (pintype "bidirectional"))
      (node (ref "R85") (pin "1") (pinfunction "1_1") (pintype "passive"))
      (node (ref "U$1") (pin "28") (pinfunction "ADC5/SCL/PCINT13_28") (pintype "bidirectional"))
    )
    (net (code "71") (name "SDA") (class "Default")
      (node (ref "0001000") (pin "7") (pinfunction "SDA_7") (pintype "bidirectional"))
      (node (ref "0001001") (pin "7") (pinfunction "SDA_7") (pintype "bidirectional"))
      (node (ref "0001010") (pin "7") (pinfunction "SDA_7") (pintype "bidirectional"))
      (node (ref "0001011") (pin "7") (pinfunction "SDA_7") (pintype "bidirectional"))
      (node (ref "0011000") (pin "7") (pinfunction "SDA_7") (pintype "bidirectional"))
      (node (ref "0011001") (pin "7") (pinfunction "SDA_7") (pintype "bidirectional"))
      (node (ref "R86") (pin "1") (pinfunction "1_1") (pintype "passive"))
      (node (ref "U$1") (pin "27") (pinfunction "ADC4/SDA/PCINT12_27") (pintype "bidirectional"))
    )
    (net (code "72") (name "SER_INVALID") (class "Default")
      (node (ref "U2") (pin "10") (pinfunction "~{INVALID}_10") (pintype "output"))
    )
    (net (code "73") (name "SIG1") (class "Default")
      (node (ref "TO_FCC") (pin "P$5") (pinfunction "5_P$5") (pintype "bidirectional"))
      (node (ref "U$1") (pin "26") (pinfunction "ADC3/PCINT11_26") (pintype "bidirectional"))
    )
    (net (code "74") (name "SIG2") (class "Default")
      (node (ref "TO_FCC") (pin "P$6") (pinfunction "6_P$6") (pintype "bidirectional"))
      (node (ref "U$1") (pin "25") (pinfunction "ADC2/PCINT10_25") (pintype "bidirectional"))
    )
    (net (code "75") (name "SIG3") (class "Default")
      (node (ref "TO_FCC") (pin "P$7") (pinfunction "7_P$7") (pintype "bidirectional"))
      (node (ref "U$1") (pin "24") (pinfunction "ADC1/PCINT9_24") (pintype "bidirectional"))
    )
    (net (code "76") (name "SIG4") (class "Default")
      (node (ref "TO_FCC") (pin "P$8") (pinfunction "8_P$8") (pintype "bidirectional"))
      (node (ref "U$1") (pin "23") (pinfunction "ADC0/PCINT8_23") (pintype "bidirectional"))
    )
    (net (code "77") (name "TX") (class "Default")
      (node (ref "U$1") (pin "3") (pinfunction "PCINT17/TXD_3") (pintype "bidirectional"))
      (node (ref "U2") (pin "11") (pinfunction "DIN_11") (pintype "input"))
    )
    (net (code "78") (name "TX12") (class "Default")
      (node (ref "TO_FCC") (pin "P$3") (pinfunction "3_P$3") (pintype "bidirectional"))
      (node (ref "U2") (pin "13") (pinfunction "DOUT_13") (pintype "output"))
    )
    (net (code "79") (name "V+") (class "Default")
      (node (ref "0001000") (pin "10") (pinfunction "VDD1_10") (pintype "bidirectional"))
      (node (ref "0001000") (pin "3") (pinfunction "VDD0_3") (pintype "bidirectional"))
      (node (ref "0001001") (pin "10") (pinfunction "VDD1_10") (pintype "bidirectional"))
      (node (ref "0001001") (pin "3") (pinfunction "VDD0_3") (pintype "bidirectional"))
      (node (ref "0001010") (pin "10") (pinfunction "VDD1_10") (pintype "bidirectional"))
      (node (ref "0001010") (pin "3") (pinfunction "VDD0_3") (pintype "bidirectional"))
      (node (ref "0001010") (pin "4") (pinfunction "AD0_4") (pintype "bidirectional"))
      (node (ref "0001011") (pin "10") (pinfunction "VDD1_10") (pintype "bidirectional"))
      (node (ref "0001011") (pin "3") (pinfunction "VDD0_3") (pintype "bidirectional"))
      (node (ref "0001011") (pin "4") (pinfunction "AD0_4") (pintype "bidirectional"))
      (node (ref "0011000") (pin "10") (pinfunction "VDD1_10") (pintype "bidirectional"))
      (node (ref "0011000") (pin "3") (pinfunction "VDD0_3") (pintype "bidirectional"))
      (node (ref "0011001") (pin "10") (pinfunction "VDD1_10") (pintype "bidirectional"))
      (node (ref "0011001") (pin "3") (pinfunction "VDD0_3") (pintype "bidirectional"))
      (node (ref "C1") (pin "1") (pinfunction "1_1") (pintype "passive"))
      (node (ref "C15") (pin "1") (pinfunction "1_1") (pintype "passive"))
      (node (ref "C16") (pin "1") (pinfunction "1_1") (pintype "passive"))
      (node (ref "C17") (pin "1") (pinfunction "1_1") (pintype "passive"))
      (node (ref "C2") (pin "1") (pinfunction "1_1") (pintype "passive"))
      (node (ref "C21") (pin "1") (pinfunction "1_1") (pintype "passive"))
      (node (ref "C22") (pin "1") (pinfunction "1_1") (pintype "passive"))
      (node (ref "C23") (pin "1") (pinfunction "1_1") (pintype "passive"))
      (node (ref "C27") (pin "1") (pinfunction "1_1") (pintype "passive"))
      (node (ref "C28") (pin "1") (pinfunction "1_1") (pintype "passive"))
      (node (ref "C29") (pin "1") (pinfunction "1_1") (pintype "passive"))
      (node (ref "C3") (pin "1") (pinfunction "1_1") (pintype "passive"))
      (node (ref "C33") (pin "1") (pinfunction "1_1") (pintype "passive"))
      (node (ref "C34") (pin "1") (pinfunction "1_1") (pintype "passive"))
      (node (ref "C35") (pin "1") (pinfunction "1_1") (pintype "passive"))
      (node (ref "C37") (pin "1") (pinfunction "1_1") (pintype "passive"))
      (node (ref "C38") (pin "1") (pinfunction "1_1") (pintype "passive"))
      (node (ref "C7") (pin "1") (pinfunction "1_1") (pintype "passive"))
      (node (ref "C8") (pin "1") (pinfunction "1_1") (pintype "passive"))
      (node (ref "C9") (pin "1") (pinfunction "1_1") (pintype "passive"))
      (node (ref "ISP1") (pin "2") (pinfunction "VCC_2") (pintype "power_in"))
      (node (ref "R85") (pin "2") (pinfunction "2_2") (pintype "passive"))
      (node (ref "R86") (pin "2") (pinfunction "2_2") (pintype "passive"))
      (node (ref "R87") (pin "2") (pinfunction "2_2") (pintype "passive"))
      (node (ref "TO_FCC") (pin "P$1") (pinfunction "1_P$1") (pintype "bidirectional"))
      (node (ref "U$1") (pin "20") (pinfunction "AVCC_20") (pintype "bidirectional"))
      (node (ref "U$1") (pin "7") (pinfunction "VCC_7") (pintype "bidirectional"))
      (node (ref "U2") (pin "15") (pinfunction "VCC_15") (pintype "power_in"))
      (node (ref "U2") (pin "16") (pinfunction "~{FORCEOFF}_16") (pintype "input"))
    )
    (net (code "80") (name "V1") (class "Default")
      (node (ref "0001000") (pin "11") (pinfunction "CH0_11") (pintype "bidirectional"))
      (node (ref "U$3") (pin "1") (pinfunction "1_1") (pintype "bidirectional"))
    )
    (net (code "81") (name "V2") (class "Default")
      (node (ref "0001000") (pin "12") (pinfunction "CH1_12") (pintype "bidirectional"))
      (node (ref "U$3") (pin "2") (pinfunction "2_2") (pintype "bidirectional"))
    )
    (net (code "82") (name "V3") (class "Default")
      (node (ref "0001000") (pin "13") (pinfunction "CH2_13") (pintype "bidirectional"))
      (node (ref "U$3") (pin "3") (pinfunction "3_3") (pintype "bidirectional"))
    )
    (net (code "83") (name "V4") (class "Default")
      (node (ref "0001000") (pin "14") (pinfunction "CH3_14") (pintype "bidirectional"))
      (node (ref "U$3") (pin "4") (pinfunction "4_4") (pintype "bidirectional"))
    )
    (net (code "84") (name "V5") (class "Default")
      (node (ref "R2") (pin "2") (pinfunction "2_2") (pintype "passive"))
      (node (ref "U$3") (pin "5") (pinfunction "5_5") (pintype "bidirectional"))
    )
    (net (code "85") (name "V6") (class "Default")
      (node (ref "R4") (pin "2") (pinfunction "2_2") (pintype "passive"))
      (node (ref "U$3") (pin "6") (pinfunction "6_6") (pintype "bidirectional"))
    )
    (net (code "86") (name "V7") (class "Default")
      (node (ref "R6") (pin "2") (pinfunction "2_2") (pintype "passive"))
      (node (ref "U$3") (pin "7") (pinfunction "7_7") (pintype "bidirectional"))
    )
    (net (code "87") (name "V8") (class "Default")
      (node (ref "R8") (pin "2") (pinfunction "2_2") (pintype "passive"))
      (node (ref "U$3") (pin "8") (pinfunction "8_8") (pintype "bidirectional"))
    )
    (net (code "88") (name "V9") (class "Default")
      (node (ref "R23") (pin "2") (pinfunction "2_2") (pintype "passive"))
      (node (ref "U$3") (pin "9") (pinfunction "9_9") (pintype "bidirectional"))
    )
    (net (code "89") (name "V10") (class "Default")
      (node (ref "R21") (pin "2") (pinfunction "2_2") (pintype "passive"))
      (node (ref "U$3") (pin "10") (pinfunction "10_10") (pintype "bidirectional"))
    )
    (net (code "90") (name "V11") (class "Default")
      (node (ref "R19") (pin "2") (pinfunction "2_2") (pintype "passive"))
      (node (ref "U$3") (pin "11") (pinfunction "11_11") (pintype "bidirectional"))
    )
    (net (code "91") (name "V12") (class "Default")
      (node (ref "R17") (pin "2") (pinfunction "2_2") (pintype "passive"))
      (node (ref "U$3") (pin "12") (pinfunction "12_12") (pintype "bidirectional"))
    )
    (net (code "92") (name "V13") (class "Default")
      (node (ref "R15") (pin "2") (pinfunction "2_2") (pintype "passive"))
      (node (ref "U$3") (pin "13") (pinfunction "13_13") (pintype "bidirectional"))
    )
    (net (code "93") (name "V14") (class "Default")
      (node (ref "R13") (pin "2") (pinfunction "2_2") (pintype "passive"))
      (node (ref "U$3") (pin "14") (pinfunction "14_14") (pintype "bidirectional"))
    )
    (net (code "94") (name "V15") (class "Default")
      (node (ref "R11") (pin "2") (pinfunction "2_2") (pintype "passive"))
      (node (ref "U$3") (pin "15") (pinfunction "15_15") (pintype "bidirectional"))
    )
    (net (code "95") (name "V16") (class "Default")
      (node (ref "R9") (pin "2") (pinfunction "2_2") (pintype "passive"))
      (node (ref "U$3") (pin "16") (pinfunction "16_16") (pintype "bidirectional"))
    )
    (net (code "96") (name "V17") (class "Default")
      (node (ref "R37") (pin "2") (pinfunction "2_2") (pintype "passive"))
      (node (ref "U$3") (pin "17") (pinfunction "17_17") (pintype "bidirectional"))
    )
    (net (code "97") (name "V18") (class "Default")
      (node (ref "R35") (pin "2") (pinfunction "2_2") (pintype "passive"))
      (node (ref "U$3") (pin "18") (pinfunction "18_18") (pintype "bidirectional"))
    )
    (net (code "98") (name "V19") (class "Default")
      (node (ref "R33") (pin "2") (pinfunction "2_2") (pintype "passive"))
      (node (ref "U$3") (pin "19") (pinfunction "19_19") (pintype "bidirectional"))
    )
    (net (code "99") (name "V20") (class "Default")
      (node (ref "R31") (pin "2") (pinfunction "2_2") (pintype "passive"))
      (node (ref "U$3") (pin "20") (pinfunction "20_20") (pintype "bidirectional"))
    )
    (net (code "100") (name "V21") (class "Default")
      (node (ref "R29") (pin "2") (pinfunction "2_2") (pintype "passive"))
      (node (ref "U$3") (pin "21") (pinfunction "21_21") (pintype "bidirectional"))
    )
    (net (code "101") (name "V22") (class "Default")
      (node (ref "R27") (pin "2") (pinfunction "2_2") (pintype "passive"))
      (node (ref "U$3") (pin "22") (pinfunction "22_22") (pintype "bidirectional"))
    )
    (net (code "102") (name "V23") (class "Default")
      (node (ref "R25") (pin "2") (pinfunction "2_2") (pintype "passive"))
      (node (ref "U$3") (pin "23") (pinfunction "23_23") (pintype "bidirectional"))
    )
    (net (code "103") (name "V24") (class "Default")
      (node (ref "R40") (pin "2") (pinfunction "2_2") (pintype "passive"))
      (node (ref "U$3") (pin "24") (pinfunction "24_24") (pintype "bidirectional"))
    )
    (net (code "104") (name "V25") (class "Default")
      (node (ref "R55") (pin "2") (pinfunction "2_2") (pintype "passive"))
      (node (ref "U$3") (pin "25") (pinfunction "25_25") (pintype "bidirectional"))
    )
    (net (code "105") (name "V26") (class "Default")
      (node (ref "R53") (pin "2") (pinfunction "2_2") (pintype "passive"))
      (node (ref "U$3") (pin "26") (pinfunction "26_26") (pintype "bidirectional"))
    )
    (net (code "106") (name "V27") (class "Default")
      (node (ref "R51") (pin "2") (pinfunction "2_2") (pintype "passive"))
      (node (ref "U$3") (pin "27") (pinfunction "27_27") (pintype "bidirectional"))
    )
    (net (code "107") (name "V28") (class "Default")
      (node (ref "R49") (pin "2") (pinfunction "2_2") (pintype "passive"))
      (node (ref "U$3") (pin "28") (pinfunction "28_28") (pintype "bidirectional"))
    )
    (net (code "108") (name "V29") (class "Default")
      (node (ref "R42") (pin "2") (pinfunction "2_2") (pintype "passive"))
      (node (ref "U$3") (pin "29") (pinfunction "29_29") (pintype "bidirectional"))
    )
    (net (code "109") (name "V30") (class "Default")
      (node (ref "R44") (pin "2") (pinfunction "2_2") (pintype "passive"))
      (node (ref "U$3") (pin "30") (pinfunction "30_30") (pintype "bidirectional"))
    )
    (net (code "110") (name "V31") (class "Default")
      (node (ref "R46") (pin "2") (pinfunction "2_2") (pintype "passive"))
      (node (ref "U$3") (pin "31") (pinfunction "31_31") (pintype "bidirectional"))
    )
    (net (code "111") (name "V32") (class "Default")
      (node (ref "R48") (pin "2") (pinfunction "2_2") (pintype "passive"))
      (node (ref "U$3") (pin "32") (pinfunction "32_32") (pintype "bidirectional"))
    )
    (net (code "112") (name "V33") (class "Default")
      (node (ref "R71") (pin "2") (pinfunction "2_2") (pintype "passive"))
      (node (ref "U$3") (pin "33") (pinfunction "33_33") (pintype "bidirectional"))
    )
    (net (code "113") (name "V34") (class "Default")
      (node (ref "R69") (pin "2") (pinfunction "2_2") (pintype "passive"))
      (node (ref "U$3") (pin "34") (pinfunction "34_34") (pintype "bidirectional"))
    )
    (net (code "114") (name "V35") (class "Default")
      (node (ref "R67") (pin "2") (pinfunction "2_2") (pintype "passive"))
      (node (ref "U$3") (pin "35") (pinfunction "35_35") (pintype "bidirectional"))
    )
    (net (code "115") (name "V36") (class "Default")
      (node (ref "R65") (pin "2") (pinfunction "2_2") (pintype "passive"))
      (node (ref "U$3") (pin "36") (pinfunction "36_36") (pintype "bidirectional"))
    )
    (net (code "116") (name "V37") (class "Default")
      (node (ref "R58") (pin "2") (pinfunction "2_2") (pintype "passive"))
      (node (ref "U$3") (pin "37") (pinfunction "37_37") (pintype "bidirectional"))
    )
    (net (code "117") (name "V38") (class "Default")
      (node (ref "R60") (pin "2") (pinfunction "2_2") (pintype "passive"))
      (node (ref "U$3") (pin "38") (pinfunction "38_38") (pintype "bidirectional"))
    )
    (net (code "118") (name "V39") (class "Default")
      (node (ref "R62") (pin "2") (pinfunction "2_2") (pintype "passive"))
      (node (ref "U$3") (pin "39") (pinfunction "39_39") (pintype "bidirectional"))
    )
    (net (code "119") (name "V40") (class "Default")
      (node (ref "R64") (pin "2") (pinfunction "2_2") (pintype "passive"))
      (node (ref "U$3") (pin "40") (pinfunction "40_40") (pintype "bidirectional"))
    )
    (net (code "120") (name "V41") (class "Default")
      (node (ref "R83") (pin "2") (pinfunction "2_2") (pintype "passive"))
      (node (ref "U$3") (pin "41") (pinfunction "41_41") (pintype "bidirectional"))
    )
    (net (code "121") (name "V42") (class "Default")
      (node (ref "R81") (pin "2") (pinfunction "2_2") (pintype "passive"))
      (node (ref "U$3") (pin "42") (pinfunction "42_42") (pintype "bidirectional"))
    )
    (net (code "122") (name "V43") (class "Default")
      (node (ref "R79") (pin "2") (pinfunction "2_2") (pintype "passive"))
      (node (ref "U$3") (pin "43") (pinfunction "43_43") (pintype "bidirectional"))
    )
    (net (code "123") (name "V44") (class "Default")
      (node (ref "R77") (pin "2") (pinfunction "2_2") (pintype "passive"))
      (node (ref "U$3") (pin "44") (pinfunction "44_44") (pintype "bidirectional"))
    )
    (net (code "124") (name "V45") (class "Default")
      (node (ref "R75") (pin "2") (pinfunction "2_2") (pintype "passive"))
      (node (ref "U$3") (pin "45") (pinfunction "45_45") (pintype "bidirectional"))
    )
    (net (code "125") (name "V46") (class "Default")
      (node (ref "R73") (pin "2") (pinfunction "2_2") (pintype "passive"))
      (node (ref "U$3") (pin "46") (pinfunction "46_46") (pintype "bidirectional"))
    )
    (net (code "126") (name "unconnected-(0001001-AD0-Pad4)") (class "Default")
      (node (ref "0001001") (pin "4") (pinfunction "AD0_4") (pintype "bidirectional"))
    )
    (net (code "127") (name "unconnected-(0001011-AD1-Pad5)") (class "Default")
      (node (ref "0001011") (pin "5") (pinfunction "AD1_5") (pintype "bidirectional"))
    )
    (net (code "128") (name "unconnected-(0011000-AD0-Pad4)") (class "Default")
      (node (ref "0011000") (pin "4") (pinfunction "AD0_4") (pintype "bidirectional"))
    )
    (net (code "129") (name "unconnected-(0011000-AD1-Pad5)") (class "Default")
      (node (ref "0011000") (pin "5") (pinfunction "AD1_5") (pintype "bidirectional"))
    )
    (net (code "130") (name "unconnected-(0011001-AD1-Pad5)") (class "Default")
      (node (ref "0011001") (pin "5") (pinfunction "AD1_5") (pintype "bidirectional"))
    )
    (net (code "131") (name "unconnected-(0011001-CH6-Pad17)") (class "Default")
      (node (ref "0011001") (pin "17") (pinfunction "CH6_17") (pintype "bidirectional"))
    )
    (net (code "132") (name "unconnected-(0011001-CH7-Pad18)") (class "Default")
      (node (ref "0011001") (pin "18") (pinfunction "CH7_18") (pintype "bidirectional"))
    )
    (net (code "133") (name "unconnected-(TO_FCC-LED1N-PadP$9)") (class "Default")
      (node (ref "TO_FCC") (pin "P$9") (pinfunction "LED1N_P$9") (pintype "bidirectional"))
    )
    (net (code "134") (name "unconnected-(TO_FCC-LED1P-PadP$10)") (class "Default")
      (node (ref "TO_FCC") (pin "P$10") (pinfunction "LED1P_P$10") (pintype "bidirectional"))
    )
    (net (code "135") (name "unconnected-(TO_FCC-LED2N-PadP$11)") (class "Default")
      (node (ref "TO_FCC") (pin "P$11") (pinfunction "LED2N_P$11") (pintype "bidirectional"))
    )
    (net (code "136") (name "unconnected-(TO_FCC-LED2P-PadP$12)") (class "Default")
      (node (ref "TO_FCC") (pin "P$12") (pinfunction "LED2P_P$12") (pintype "bidirectional"))
    )
    (net (code "137") (name "unconnected-(U$1-AREF-Pad21)") (class "Default")
      (node (ref "U$1") (pin "21") (pinfunction "AREF_21") (pintype "bidirectional"))
    )
    (net (code "138") (name "unconnected-(U$1-OC1A{slash}PCINT1-Pad15)") (class "Default")
      (node (ref "U$1") (pin "15") (pinfunction "OC1A/PCINT1_15") (pintype "bidirectional"))
    )
    (net (code "139") (name "unconnected-(U$1-PCINT0{slash}CLKO{slash}ICP1-Pad14)") (class "Default")
      (node (ref "U$1") (pin "14") (pinfunction "PCINT0/CLKO/ICP1_14") (pintype "bidirectional"))
    )
    (net (code "140") (name "unconnected-(U$1-PCINT18{slash}INT0-Pad4)") (class "Default")
      (node (ref "U$1") (pin "4") (pinfunction "PCINT18/INT0_4") (pintype "bidirectional"))
    )
    (net (code "141") (name "unconnected-(U$1-PCINT19{slash}OC2B{slash}INT1-Pad5)") (class "Default")
      (node (ref "U$1") (pin "5") (pinfunction "PCINT19/OC2B/INT1_5") (pintype "bidirectional"))
    )
    (net (code "142") (name "unconnected-(U$1-PCINT20{slash}XCK{slash}T0-Pad6)") (class "Default")
      (node (ref "U$1") (pin "6") (pinfunction "PCINT20/XCK/T0_6") (pintype "bidirectional"))
    )
    (net (code "143") (name "unconnected-(U$1-PCINT21{slash}OC0B{slash}T1-Pad11)") (class "Default")
      (node (ref "U$1") (pin "11") (pinfunction "PCINT21/OC0B/T1_11") (pintype "bidirectional"))
    )
    (net (code "144") (name "unconnected-(U$1-PCINT22{slash}OC0A{slash}AIN0-Pad12)") (class "Default")
      (node (ref "U$1") (pin "12") (pinfunction "PCINT22/OC0A/AIN0_12") (pintype "bidirectional"))
    )
    (net (code "145") (name "unconnected-(U$1-PCINT23{slash}AIN1-Pad13)") (class "Default")
      (node (ref "U$1") (pin "13") (pinfunction "PCINT23/AIN1_13") (pintype "bidirectional"))
    )
    (net (code "146") (name "unconnected-(U$1-SS{slash}OC1B{slash}PCINT2-Pad16)") (class "Default")
      (node (ref "U$1") (pin "16") (pinfunction "SS/OC1B/PCINT2_16") (pintype "bidirectional"))
    )
    (net (code "147") (name "unconnected-(U$3-Pad48)") (class "Default")
      (node (ref "U$3") (pin "48") (pinfunction "48_48") (pintype "bidirectional"))
    )
  )
)
